# design.net
KiCad netlist of a schematic drawn in EasyEDA
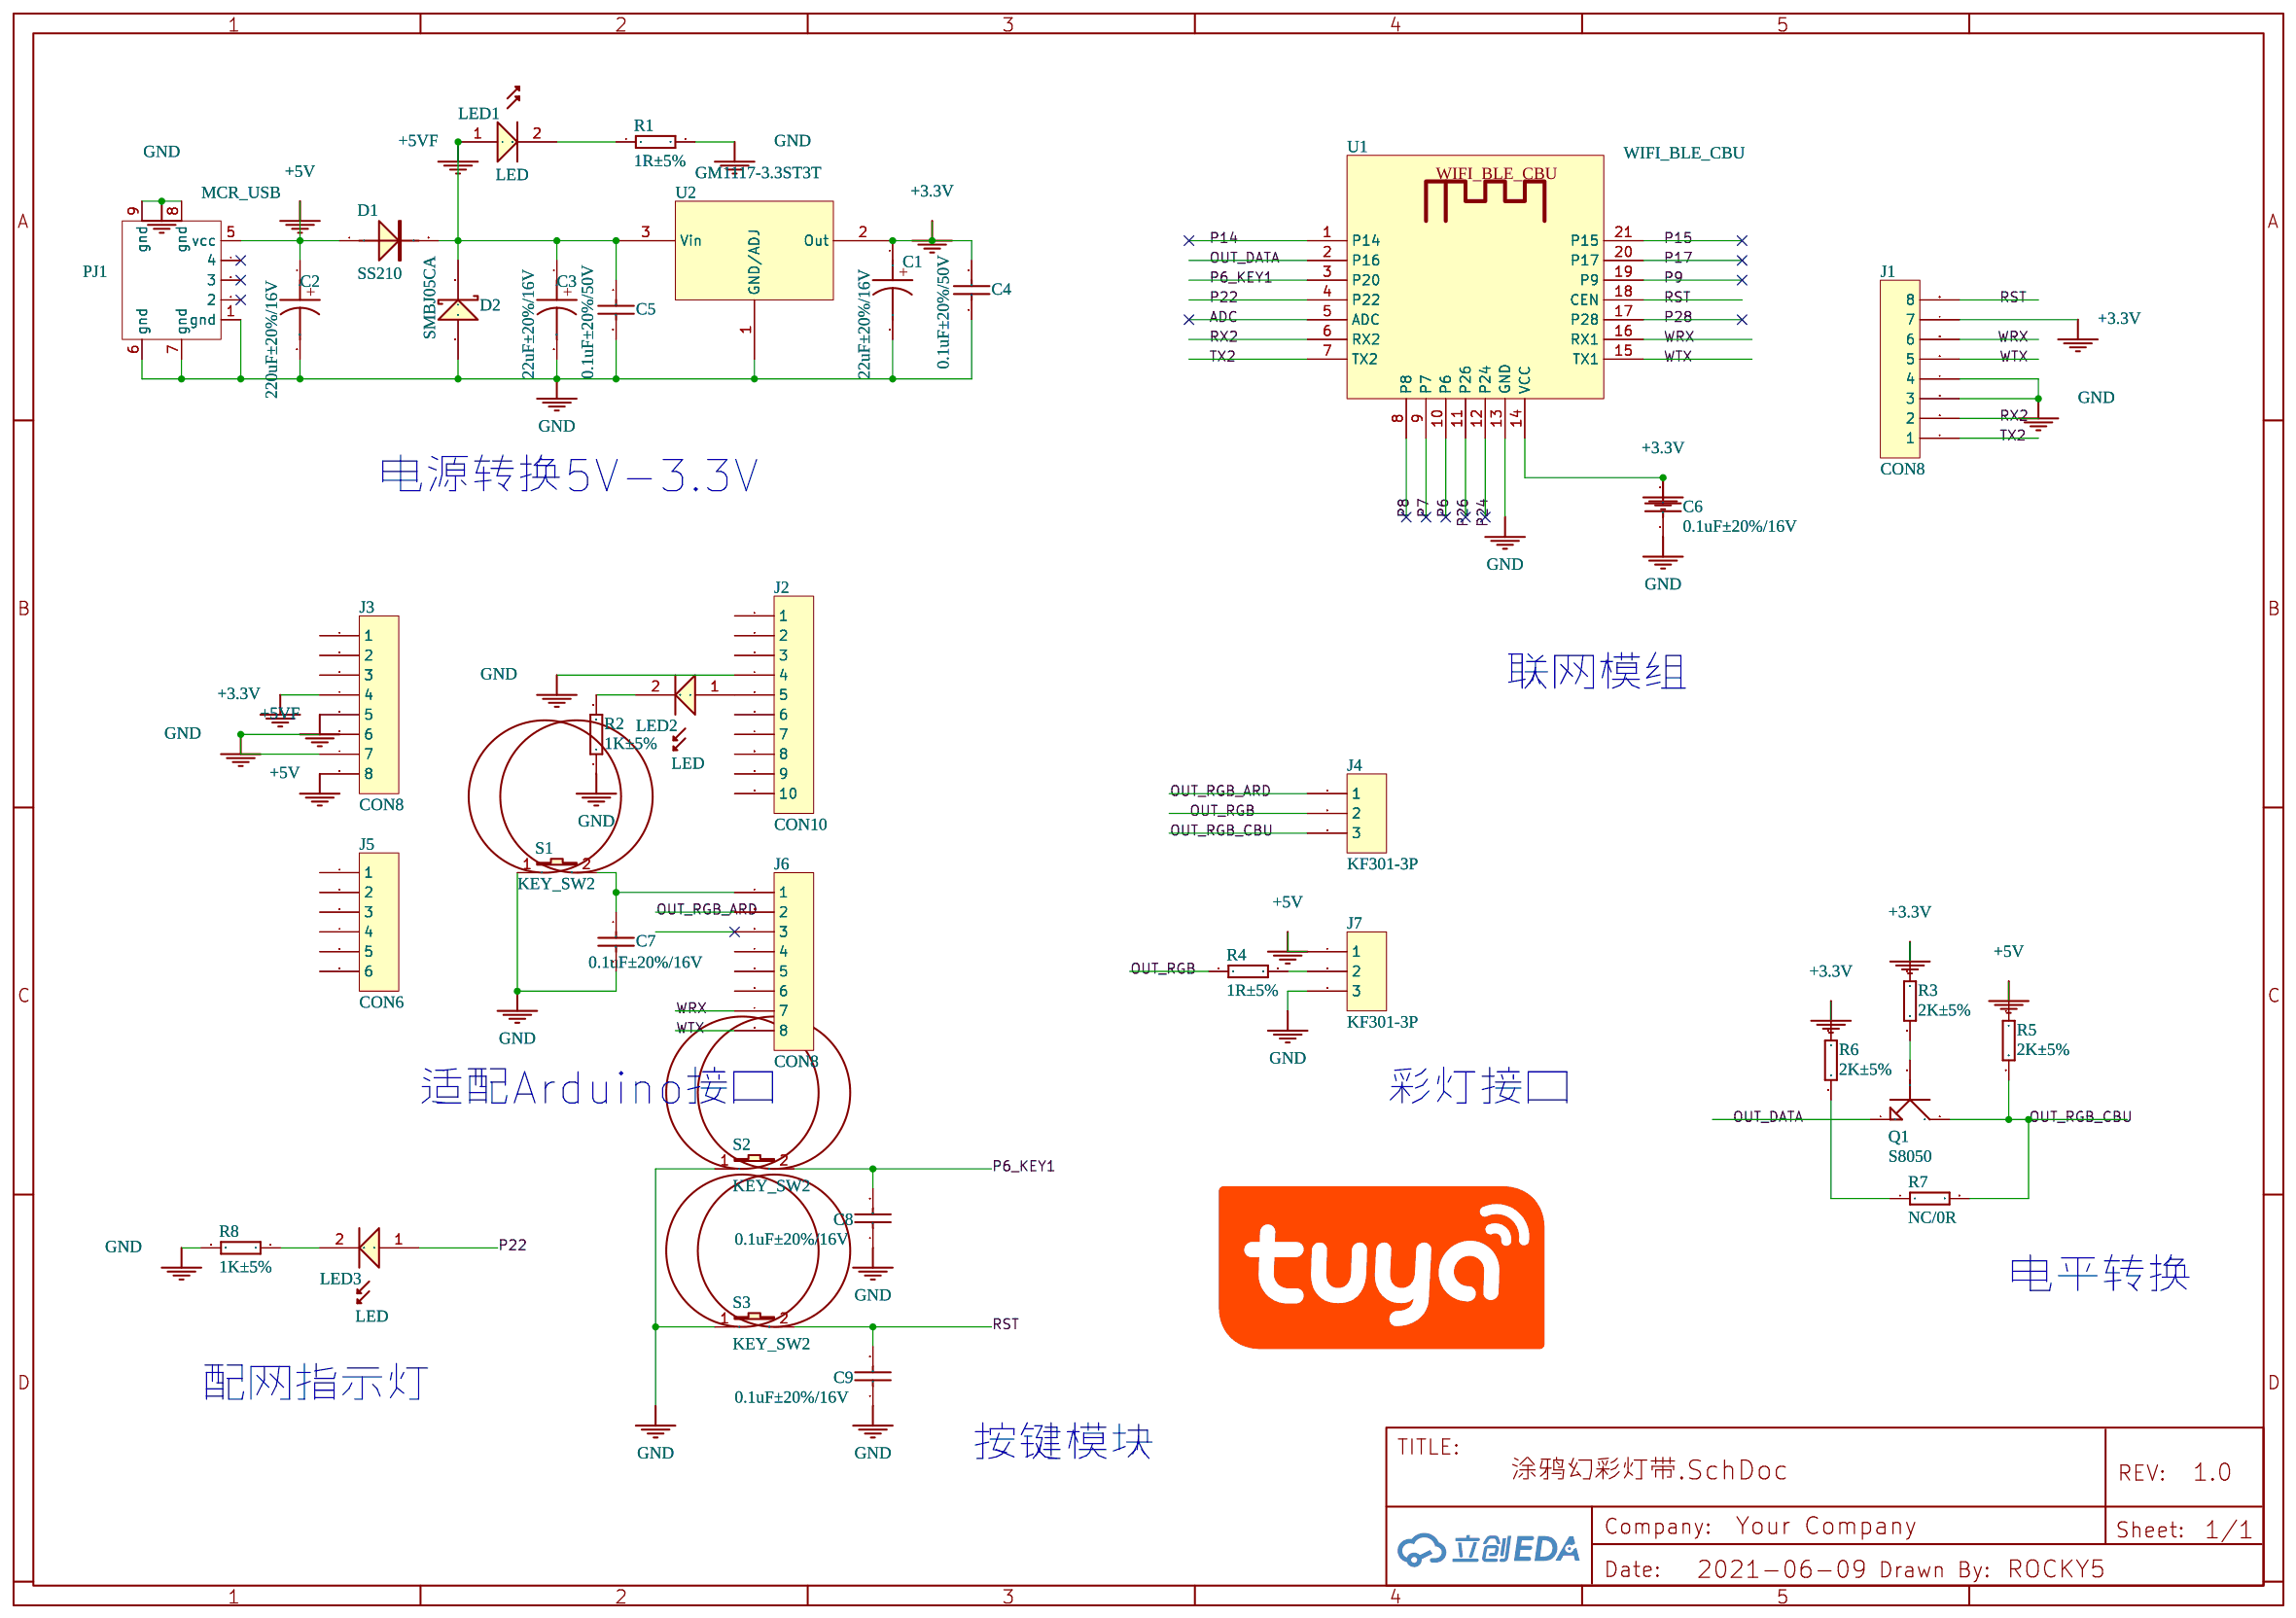
[diagram p0: schematic sheet]

(export (version "E")
  (design (tool "Eeschema 10.0.6"))
  (components
    (comp (ref "C1") (value "22uF±20%/16V") (libsource (lib "") (part "Unknown_420_-640")))
    (comp (ref "C2") (value "220uF±20%/16V") (libsource (lib "") (part "Unknown_120_-630")))
    (comp (ref "C3") (value "22uF±20%/16V") (libsource (lib "") (part "Unknown_250_-630")))
    (comp (ref "C4") (value "0.1uF±20%/50V") (libsource (lib "") (part "Unknown_460_-630")))
    (comp (ref "C5") (value "0.1uF±20%/50V") (libsource (lib "") (part "Unknown_280_-620")))
    (comp (ref "C6") (value "0.1uF±20%/16V") (libsource (lib "") (part "Unknown_830_-510")))
    (comp (ref "C7") (value "0.1uF±20%/16V") (libsource (lib "") (part "Unknown_280_-300")))
    (comp (ref "C8") (value "0.1uF±20%/16V") (libsource (lib "") (part "Unknown_430_-150")))
    (comp (ref "C9") (value "0.1uF±20%/16V") (libsource (lib "") (part "Unknown_430_-70")))
    (comp (ref "D1") (value "SS210") (libsource (lib "") (part "Unknown_170_-650")))
    (comp (ref "D2") (value "SMBJ05CA") (libsource (lib "") (part "Unknown_200_-610")))
    (comp (ref "J1") (value "CON8") (libsource (lib "") (part "Unknown_950_-540")))
    (comp (ref "J2") (value "CON10") (libsource (lib "") (part "Unknown_370_-470")))
    (comp (ref "J3") (value "CON8") (libsource (lib "") (part "Unknown_160_-460")))
    (comp (ref "J4") (value "KF301-3P") (libsource (lib "") (part "Unknown_660_-380")))
    (comp (ref "J5") (value "CON6") (libsource (lib "") (part "Unknown_160_-340")))
    (comp (ref "J6") (value "CON8") (libsource (lib "") (part "Unknown_370_-330")))
    (comp (ref "J7") (value "KF301-3P") (libsource (lib "") (part "Unknown_660_-300")))
    (comp (ref "LED1") (value "LED") (libsource (lib "") (part "Unknown_230_-710")))
    (comp (ref "LED2") (value "LED") (libsource (lib "") (part "Unknown_330_-410")))
    (comp (ref "LED3") (value "LED") (libsource (lib "") (part "Unknown_170_-130")))
    (comp (ref "PJ1") (value "MCR_USB") (libsource (lib "") (part "Unknown_40_-660")))
    (comp (ref "Q1") (value "S8050") (libsource (lib "") (part "Unknown_955_-225")))
    (comp (ref "R1") (value "1R±5%") (libsource (lib "") (part "Unknown_310_-700")))
    (comp (ref "R2") (value "1K±5%") (libsource (lib "") (part "Unknown_280_-400")))
    (comp (ref "R3") (value "2K±5%") (libsource (lib "") (part "Unknown_945_-265")))
    (comp (ref "R4") (value "1R±5%") (libsource (lib "") (part "Unknown_610_-280")))
    (comp (ref "R5") (value "2K±5%") (libsource (lib "") (part "Unknown_995_-245")))
    (comp (ref "R6") (value "2K±5%") (libsource (lib "") (part "Unknown_905_-235")))
    (comp (ref "R7") (value "NC/0R") (libsource (lib "") (part "Unknown_955_-165")))
    (comp (ref "R8") (value "1K±5%") (libsource (lib "") (part "Unknown_100_-140")))
    (comp (ref "S1") (value "KEY_SW2") (libsource (lib "") (part "Unknown_250_-340")))
    (comp (ref "S2") (value "KEY_SW2") (libsource (lib "") (part "Unknown_350_-190")))
    (comp (ref "S3") (value "KEY_SW2") (libsource (lib "") (part "Unknown_350_-110")))
    (comp (ref "U1") (value "WIFI_BLE_CBU") (libsource (lib "") (part "Unknown_660_-570")))
    (comp (ref "U2") (value "GM1117-3.3ST3T") (libsource (lib "") (part "Unknown_360_-640")))
  )
  (nets
    (net (code "1") (name "+3.3V") (class "Default")
      (node (ref "C1") (pin "1") (pinfunction "1_1") (pintype "unspecified"))
      (node (ref "C4") (pin "1") (pinfunction "1_1") (pintype "unspecified"))
      (node (ref "C6") (pin "2") (pinfunction "2_2") (pintype "unspecified"))
      (node (ref "J1") (pin "7") (pinfunction "7_7") (pintype "unspecified"))
      (node (ref "J3") (pin "4") (pinfunction "4_4") (pintype "unspecified"))
      (node (ref "R3") (pin "1") (pinfunction "1_1") (pintype "unspecified"))
      (node (ref "R6") (pin "1") (pinfunction "1_1") (pintype "unspecified"))
      (node (ref "U1") (pin "14") (pinfunction "VCC_14") (pintype "unspecified"))
      (node (ref "U2") (pin "2") (pinfunction "Out_2") (pintype "unspecified"))
    )
    (net (code "2") (name "+5V") (class "Default")
      (node (ref "C2") (pin "1") (pinfunction "1_1") (pintype "unspecified"))
      (node (ref "D1") (pin "1") (pinfunction "1_1") (pintype "unspecified"))
      (node (ref "J3") (pin "8") (pinfunction "8_8") (pintype "unspecified"))
      (node (ref "J7") (pin "1") (pinfunction "1_1") (pintype "unspecified"))
      (node (ref "PJ1") (pin "5") (pinfunction "vcc_5") (pintype "unspecified"))
      (node (ref "R5") (pin "1") (pinfunction "1_1") (pintype "unspecified"))
    )
    (net (code "3") (name "+5VF") (class "Default")
      (node (ref "C3") (pin "1") (pinfunction "1_1") (pintype "unspecified"))
      (node (ref "C5") (pin "1") (pinfunction "1_1") (pintype "unspecified"))
      (node (ref "D1") (pin "2") (pinfunction "2_2") (pintype "unspecified"))
      (node (ref "D2") (pin "2") (pinfunction "K_2") (pintype "unspecified"))
      (node (ref "J3") (pin "5") (pinfunction "5_5") (pintype "unspecified"))
      (node (ref "LED1") (pin "1") (pinfunction "1_1") (pintype "unspecified"))
      (node (ref "U2") (pin "3") (pinfunction "Vin_3") (pintype "unspecified"))
    )
    (net (code "4") (name "/ADC") (class "Default")
      (node (ref "U1") (pin "5") (pinfunction "ADC_5") (pintype "unspecified+no_connect"))
    )
    (net (code "5") (name "/OUT_DATA") (class "Default")
      (node (ref "Q1") (pin "1") (pinfunction "E_1") (pintype "unspecified"))
      (node (ref "R6") (pin "2") (pinfunction "2_2") (pintype "unspecified"))
      (node (ref "R7") (pin "1") (pinfunction "1_1") (pintype "unspecified"))
      (node (ref "U1") (pin "2") (pinfunction "P16_2") (pintype "unspecified"))
    )
    (net (code "6") (name "/OUT_RGB") (class "Default")
      (node (ref "J4") (pin "2") (pinfunction "2_2") (pintype "unspecified"))
      (node (ref "R4") (pin "1") (pinfunction "1_1") (pintype "unspecified"))
    )
    (net (code "7") (name "/OUT_RGB_ARD") (class "Default")
      (node (ref "J4") (pin "1") (pinfunction "1_1") (pintype "unspecified"))
      (node (ref "J6") (pin "2") (pinfunction "2_2") (pintype "unspecified"))
    )
    (net (code "8") (name "/OUT_RGB_CBU") (class "Default")
      (node (ref "J4") (pin "3") (pinfunction "3_3") (pintype "unspecified"))
      (node (ref "Q1") (pin "3") (pinfunction "C_3") (pintype "unspecified"))
      (node (ref "R5") (pin "2") (pinfunction "2_2") (pintype "unspecified"))
      (node (ref "R7") (pin "2") (pinfunction "2_2") (pintype "unspecified"))
    )
    (net (code "9") (name "/P6") (class "Default")
      (node (ref "U1") (pin "10") (pinfunction "P6_10") (pintype "unspecified+no_connect"))
    )
    (net (code "10") (name "/P6_KEY1") (class "Default")
      (node (ref "C8") (pin "2") (pinfunction "2_2") (pintype "unspecified"))
      (node (ref "S2") (pin "2") (pinfunction "2_2") (pintype "unspecified"))
      (node (ref "U1") (pin "3") (pinfunction "P20_3") (pintype "unspecified"))
    )
    (net (code "11") (name "/P7") (class "Default")
      (node (ref "U1") (pin "9") (pinfunction "P7_9") (pintype "unspecified+no_connect"))
    )
    (net (code "12") (name "/P8") (class "Default")
      (node (ref "U1") (pin "8") (pinfunction "P8_8") (pintype "unspecified+no_connect"))
    )
    (net (code "13") (name "/P9") (class "Default")
      (node (ref "U1") (pin "19") (pinfunction "P9_19") (pintype "unspecified+no_connect"))
    )
    (net (code "14") (name "/P14") (class "Default")
      (node (ref "U1") (pin "1") (pinfunction "P14_1") (pintype "unspecified+no_connect"))
    )
    (net (code "15") (name "/P15") (class "Default")
      (node (ref "U1") (pin "21") (pinfunction "P15_21") (pintype "unspecified+no_connect"))
    )
    (net (code "16") (name "/P17") (class "Default")
      (node (ref "U1") (pin "20") (pinfunction "P17_20") (pintype "unspecified+no_connect"))
    )
    (net (code "17") (name "/P22") (class "Default")
      (node (ref "LED3") (pin "1") (pinfunction "1_1") (pintype "unspecified"))
      (node (ref "U1") (pin "4") (pinfunction "P22_4") (pintype "unspecified"))
    )
    (net (code "18") (name "/P24") (class "Default")
      (node (ref "U1") (pin "12") (pinfunction "P24_12") (pintype "unspecified+no_connect"))
    )
    (net (code "19") (name "/P26") (class "Default")
      (node (ref "U1") (pin "11") (pinfunction "P26_11") (pintype "unspecified+no_connect"))
    )
    (net (code "20") (name "/P28") (class "Default")
      (node (ref "U1") (pin "17") (pinfunction "P28_17") (pintype "unspecified+no_connect"))
    )
    (net (code "21") (name "/RST") (class "Default")
      (node (ref "C9") (pin "2") (pinfunction "2_2") (pintype "unspecified"))
      (node (ref "J1") (pin "8") (pinfunction "8_8") (pintype "unspecified"))
      (node (ref "S3") (pin "2") (pinfunction "2_2") (pintype "unspecified"))
      (node (ref "U1") (pin "18") (pinfunction "CEN_18") (pintype "unspecified"))
    )
    (net (code "22") (name "/RX2") (class "Default")
      (node (ref "J1") (pin "2") (pinfunction "2_2") (pintype "unspecified"))
      (node (ref "U1") (pin "6") (pinfunction "RX2_6") (pintype "unspecified"))
    )
    (net (code "23") (name "/TX2") (class "Default")
      (node (ref "J1") (pin "1") (pinfunction "1_1") (pintype "unspecified"))
      (node (ref "U1") (pin "7") (pinfunction "TX2_7") (pintype "unspecified"))
    )
    (net (code "24") (name "/WRX") (class "Default")
      (node (ref "J1") (pin "6") (pinfunction "6_6") (pintype "unspecified"))
      (node (ref "J6") (pin "7") (pinfunction "7_7") (pintype "unspecified"))
      (node (ref "U1") (pin "16") (pinfunction "RX1_16") (pintype "unspecified"))
    )
    (net (code "25") (name "/WTX") (class "Default")
      (node (ref "J1") (pin "5") (pinfunction "5_5") (pintype "unspecified"))
      (node (ref "J6") (pin "8") (pinfunction "8_8") (pintype "unspecified"))
      (node (ref "U1") (pin "15") (pinfunction "TX1_15") (pintype "unspecified"))
    )
    (net (code "26") (name "GND") (class "Default")
      (node (ref "C1") (pin "2") (pinfunction "2_2") (pintype "unspecified"))
      (node (ref "C2") (pin "2") (pinfunction "2_2") (pintype "unspecified"))
      (node (ref "C3") (pin "2") (pinfunction "2_2") (pintype "unspecified"))
      (node (ref "C4") (pin "2") (pinfunction "2_2") (pintype "unspecified"))
      (node (ref "C5") (pin "2") (pinfunction "2_2") (pintype "unspecified"))
      (node (ref "C6") (pin "1") (pinfunction "1_1") (pintype "unspecified"))
      (node (ref "C7") (pin "2") (pinfunction "2_2") (pintype "unspecified"))
      (node (ref "C8") (pin "1") (pinfunction "1_1") (pintype "unspecified"))
      (node (ref "C9") (pin "1") (pinfunction "1_1") (pintype "unspecified"))
      (node (ref "D2") (pin "1") (pinfunction "A_1") (pintype "unspecified"))
      (node (ref "J1") (pin "3") (pinfunction "3_3") (pintype "unspecified"))
      (node (ref "J1") (pin "4") (pinfunction "4_4") (pintype "unspecified"))
      (node (ref "J2") (pin "4") (pinfunction "4_4") (pintype "unspecified"))
      (node (ref "J3") (pin "6") (pinfunction "6_6") (pintype "unspecified"))
      (node (ref "J3") (pin "7") (pinfunction "7_7") (pintype "unspecified"))
      (node (ref "J7") (pin "3") (pinfunction "3_3") (pintype "unspecified"))
      (node (ref "PJ1") (pin "1") (pinfunction "gnd_1") (pintype "unspecified"))
      (node (ref "PJ1") (pin "6") (pinfunction "gnd_6") (pintype "unspecified"))
      (node (ref "PJ1") (pin "7") (pinfunction "gnd_7") (pintype "unspecified"))
      (node (ref "PJ1") (pin "8") (pinfunction "gnd_8") (pintype "unspecified"))
      (node (ref "PJ1") (pin "9") (pinfunction "gnd_9") (pintype "unspecified"))
      (node (ref "R1") (pin "2") (pinfunction "2_2") (pintype "unspecified"))
      (node (ref "R2") (pin "1") (pinfunction "1_1") (pintype "unspecified"))
      (node (ref "R8") (pin "2") (pinfunction "2_2") (pintype "unspecified"))
      (node (ref "S1") (pin "1") (pinfunction "1_1") (pintype "unspecified"))
      (node (ref "S2") (pin "1") (pinfunction "1_1") (pintype "unspecified"))
      (node (ref "S3") (pin "1") (pinfunction "1_1") (pintype "unspecified"))
      (node (ref "U1") (pin "13") (pinfunction "GND_13") (pintype "unspecified"))
      (node (ref "U2") (pin "1") (pinfunction "GND/ADJ_1") (pintype "unspecified"))
    )
    (net (code "27") (name "Net-(C7-Pad1)") (class "Default")
      (node (ref "C7") (pin "1") (pinfunction "1_1") (pintype "unspecified"))
      (node (ref "J6") (pin "1") (pinfunction "1_1") (pintype "unspecified"))
      (node (ref "S1") (pin "2") (pinfunction "2_2") (pintype "unspecified"))
    )
    (net (code "28") (name "Net-(J2-Pad5)") (class "Default")
      (node (ref "J2") (pin "5") (pinfunction "5_5") (pintype "unspecified"))
      (node (ref "LED2") (pin "1") (pinfunction "1_1") (pintype "unspecified"))
    )
    (net (code "29") (name "Net-(J7-Pad2)") (class "Default")
      (node (ref "J7") (pin "2") (pinfunction "2_2") (pintype "unspecified"))
      (node (ref "R4") (pin "2") (pinfunction "2_2") (pintype "unspecified"))
    )
    (net (code "30") (name "Net-(LED1-Pad2)") (class "Default")
      (node (ref "LED1") (pin "2") (pinfunction "2_2") (pintype "unspecified"))
      (node (ref "R1") (pin "1") (pinfunction "1_1") (pintype "unspecified"))
    )
    (net (code "31") (name "Net-(LED2-Pad2)") (class "Default")
      (node (ref "LED2") (pin "2") (pinfunction "2_2") (pintype "unspecified"))
      (node (ref "R2") (pin "2") (pinfunction "2_2") (pintype "unspecified"))
    )
    (net (code "32") (name "Net-(LED3-Pad2)") (class "Default")
      (node (ref "LED3") (pin "2") (pinfunction "2_2") (pintype "unspecified"))
      (node (ref "R8") (pin "1") (pinfunction "1_1") (pintype "unspecified"))
    )
    (net (code "33") (name "Net-(Q1-B)") (class "Default")
      (node (ref "Q1") (pin "2") (pinfunction "B_2") (pintype "input"))
      (node (ref "R3") (pin "2") (pinfunction "2_2") (pintype "unspecified"))
    )
    (net (code "34") (name "unconnected-(J2-Pad1)") (class "Default")
      (node (ref "J2") (pin "1") (pinfunction "1_1") (pintype "unspecified"))
    )
    (net (code "35") (name "unconnected-(J2-Pad2)") (class "Default")
      (node (ref "J2") (pin "2") (pinfunction "2_2") (pintype "unspecified"))
    )
    (net (code "36") (name "unconnected-(J2-Pad3)") (class "Default")
      (node (ref "J2") (pin "3") (pinfunction "3_3") (pintype "unspecified"))
    )
    (net (code "37") (name "unconnected-(J2-Pad6)") (class "Default")
      (node (ref "J2") (pin "6") (pinfunction "6_6") (pintype "unspecified"))
    )
    (net (code "38") (name "unconnected-(J2-Pad7)") (class "Default")
      (node (ref "J2") (pin "7") (pinfunction "7_7") (pintype "unspecified"))
    )
    (net (code "39") (name "unconnected-(J2-Pad8)") (class "Default")
      (node (ref "J2") (pin "8") (pinfunction "8_8") (pintype "unspecified"))
    )
    (net (code "40") (name "unconnected-(J2-Pad9)") (class "Default")
      (node (ref "J2") (pin "9") (pinfunction "9_9") (pintype "unspecified"))
    )
    (net (code "41") (name "unconnected-(J2-Pad10)") (class "Default")
      (node (ref "J2") (pin "10") (pinfunction "10_10") (pintype "unspecified"))
    )
    (net (code "42") (name "unconnected-(J3-Pad1)") (class "Default")
      (node (ref "J3") (pin "1") (pinfunction "1_1") (pintype "unspecified"))
    )
    (net (code "43") (name "unconnected-(J3-Pad2)") (class "Default")
      (node (ref "J3") (pin "2") (pinfunction "2_2") (pintype "unspecified"))
    )
    (net (code "44") (name "unconnected-(J3-Pad3)") (class "Default")
      (node (ref "J3") (pin "3") (pinfunction "3_3") (pintype "unspecified"))
    )
    (net (code "45") (name "unconnected-(J5-Pad1)") (class "Default")
      (node (ref "J5") (pin "1") (pinfunction "1_1") (pintype "unspecified"))
    )
    (net (code "46") (name "unconnected-(J5-Pad2)") (class "Default")
      (node (ref "J5") (pin "2") (pinfunction "2_2") (pintype "unspecified"))
    )
    (net (code "47") (name "unconnected-(J5-Pad3)") (class "Default")
      (node (ref "J5") (pin "3") (pinfunction "3_3") (pintype "unspecified"))
    )
    (net (code "48") (name "unconnected-(J5-Pad4)") (class "Default")
      (node (ref "J5") (pin "4") (pinfunction "4_4") (pintype "unspecified"))
    )
    (net (code "49") (name "unconnected-(J5-Pad5)") (class "Default")
      (node (ref "J5") (pin "5") (pinfunction "5_5") (pintype "unspecified"))
    )
    (net (code "50") (name "unconnected-(J5-Pad6)") (class "Default")
      (node (ref "J5") (pin "6") (pinfunction "6_6") (pintype "unspecified"))
    )
    (net (code "51") (name "unconnected-(J6-Pad3)") (class "Default")
      (node (ref "J6") (pin "3") (pinfunction "3_3") (pintype "unspecified+no_connect"))
    )
    (net (code "52") (name "unconnected-(J6-Pad4)") (class "Default")
      (node (ref "J6") (pin "4") (pinfunction "4_4") (pintype "unspecified"))
    )
    (net (code "53") (name "unconnected-(J6-Pad5)") (class "Default")
      (node (ref "J6") (pin "5") (pinfunction "5_5") (pintype "unspecified"))
    )
    (net (code "54") (name "unconnected-(J6-Pad6)") (class "Default")
      (node (ref "J6") (pin "6") (pinfunction "6_6") (pintype "unspecified"))
    )
    (net (code "55") (name "unconnected-(PJ1-Pad2)") (class "Default")
      (node (ref "PJ1") (pin "2") (pinfunction "2_2") (pintype "unspecified+no_connect"))
    )
    (net (code "56") (name "unconnected-(PJ1-Pad3)") (class "Default")
      (node (ref "PJ1") (pin "3") (pinfunction "3_3") (pintype "unspecified+no_connect"))
    )
    (net (code "57") (name "unconnected-(PJ1-Pad4)") (class "Default")
      (node (ref "PJ1") (pin "4") (pinfunction "4_4") (pintype "unspecified+no_connect"))
    )
  )
)
